# Controller.net
KiCad netlist of a schematic drawn in Altium Designer
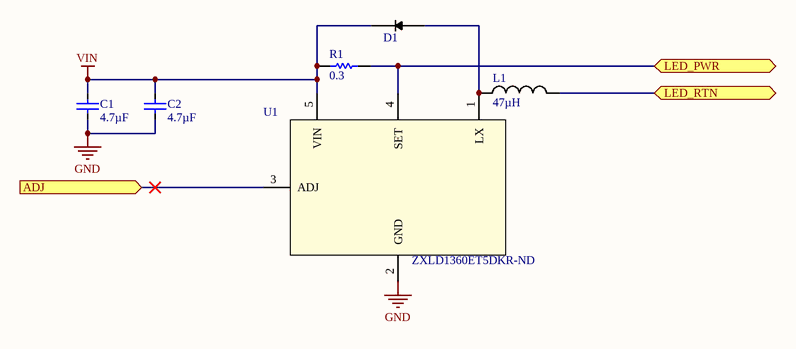
[diagram p0: Controller.SchDoc]

(export (version "E")
  (design (tool "Eeschema 10.0.6"))
  (components
    (comp (ref "C1")
      (value "4.7µF")
      (footprint "CAP_1206")
      (description "Capacitor")
      (fields
        (field (name "MANUFACTURER") "TDK Corporation")
        (field (name "MANUFACTURER PART NUMBER") "C3216X7R1V475M160AE")
      )
      (libsource (lib "RUssery") (part "CAPACITOR"))
    )
    (comp (ref "C2")
      (value "4.7µF")
      (footprint "CAP_1206")
      (description "Capacitor")
      (fields
        (field (name "MANUFACTURER") "TDK Corporation")
        (field (name "MANUFACTURER PART NUMBER") "C3216X7R1V475M160AE")
      )
      (libsource (lib "RUssery") (part "CAPACITOR"))
    )
    (comp (ref "D1")
      (value "DIODE")
      (footprint "DO-214AA(SMB)")
      (description "DIODE SCHOTTKY 40V 2A SMB")
      (libsource (lib "RUssery") (part "DIODE"))
    )
    (comp (ref "L1")
      (value "47µH")
      (footprint "INDUCTOR_BOURNS_SRN8040")
      (fields
        (field (name "TOLERANCE") "±20%")
        (field (name "MANUFACTURER") "Bourns Inc.")
        (field (name "MANUFACTURER PART NUMBER") "SRN8040-470M")
      )
      (libsource (lib "RUssery") (part "INDUCTOR"))
    )
    (comp (ref "R1")
      (value "0.3")
      (footprint "RES_0805")
      (description "Resistor")
      (fields (field (name "TOLERANCE") "±5%") (field (name "MANUFACTURER PART NUMBER") "RLP73N2AR30JTD"))
      (libsource (lib "RUssery") (part "RESISTOR"))
    )
    (comp (ref "U1")
      (value "ZXLD1360")
      (footprint "SOT95P245X110-5N")
      (fields (field (name "SUPPLIER PART NUMBER 1") "ZXLD1360ET5DKR-ND"))
      (libsource (lib "RUssery") (part "ZXLD1360"))
    )
  )
  (nets
    (net (code "1") (name "/ADJ") (class "Default")
      (node (ref "U1") (pin "3") (pinfunction "ADJ_3") (pintype "power_in"))
    )
    (net (code "2") (name "/LED_PWR") (class "Default")
      (node (ref "R1") (pin "2") (pinfunction "2_2") (pintype "passive"))
      (node (ref "U1") (pin "4") (pinfunction "SET_4") (pintype "power_in"))
    )
    (net (code "3") (name "/LED_RTN") (class "Default")
      (node (ref "L1") (pin "2") (pinfunction "2_2") (pintype "passive"))
    )
    (net (code "4") (name "GND") (class "Default")
      (node (ref "C1") (pin "2") (pinfunction "2_2") (pintype "passive"))
      (node (ref "C2") (pin "2") (pinfunction "2_2") (pintype "passive"))
      (node (ref "U1") (pin "2") (pinfunction "GND_2") (pintype "power_in"))
    )
    (net (code "5") (name "Net-(D1-K)") (class "Default")
      (node (ref "D1") (pin "2") (pinfunction "K_2") (pintype "power_in"))
      (node (ref "L1") (pin "1") (pinfunction "1_1") (pintype "passive"))
      (node (ref "U1") (pin "1") (pinfunction "LX_1") (pintype "power_in"))
    )
    (net (code "6") (name "VIN") (class "Default")
      (node (ref "C1") (pin "1") (pinfunction "1_1") (pintype "passive"))
      (node (ref "C2") (pin "1") (pinfunction "1_1") (pintype "passive"))
      (node (ref "D1") (pin "1") (pinfunction "A_1") (pintype "power_in"))
      (node (ref "R1") (pin "1") (pinfunction "1_1") (pintype "passive"))
      (node (ref "U1") (pin "5") (pinfunction "VIN_5") (pintype "power_in"))
    )
  )
)
